# Braille_Cell.net
KiCad netlist of a schematic drawn in EAGLE
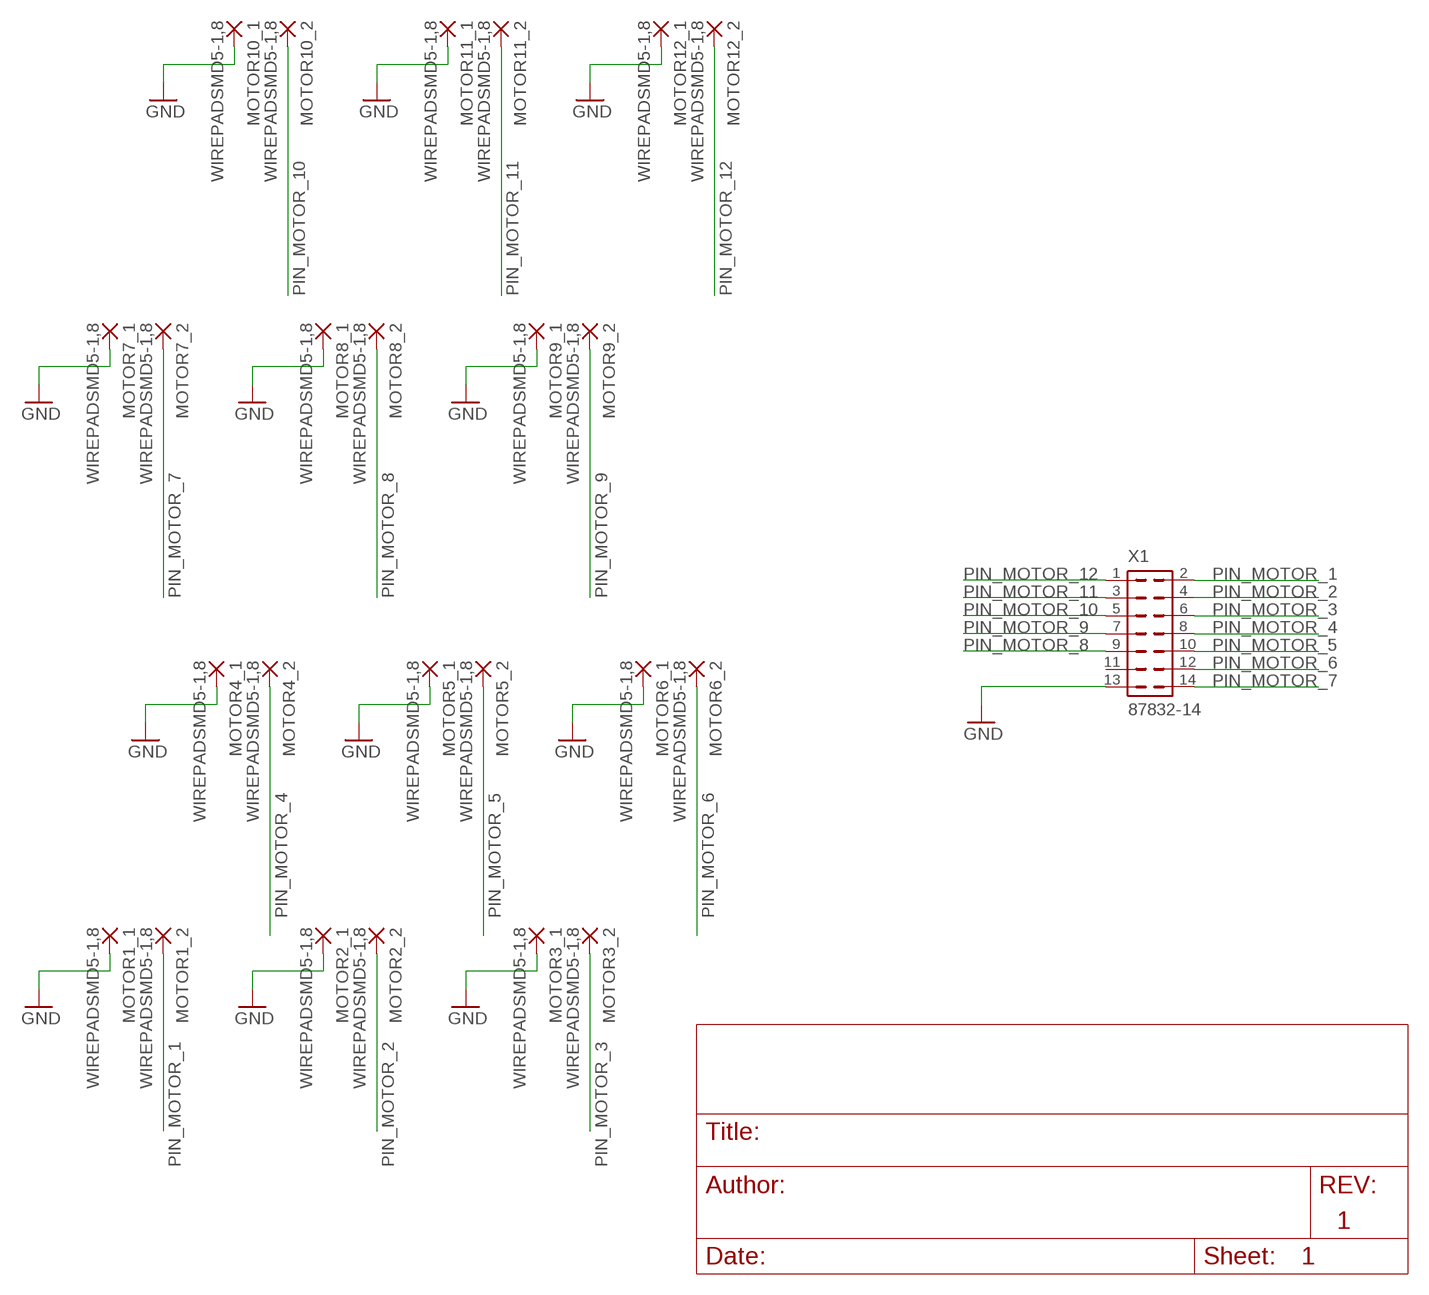
[diagram p0: schematic, sheet 1]

(export (version "E")
  (design (tool "Eeschema 10.0.6"))
  (components
    (comp (ref "MOTOR1_1")
      (value "WIREPADSMD5-1,8")
      (footprint "eagle-import:5-1,8")
      (libsource (lib "eagle-import") (part "WIREPADSMD5-1,8"))
    )
    (comp (ref "MOTOR1_2")
      (value "WIREPADSMD5-1,8")
      (footprint "eagle-import:5-1,8")
      (libsource (lib "eagle-import") (part "WIREPADSMD5-1,8"))
    )
    (comp (ref "MOTOR2_1")
      (value "WIREPADSMD5-1,8")
      (footprint "eagle-import:5-1,8")
      (libsource (lib "eagle-import") (part "WIREPADSMD5-1,8"))
    )
    (comp (ref "MOTOR2_2")
      (value "WIREPADSMD5-1,8")
      (footprint "eagle-import:5-1,8")
      (libsource (lib "eagle-import") (part "WIREPADSMD5-1,8"))
    )
    (comp (ref "MOTOR3_1")
      (value "WIREPADSMD5-1,8")
      (footprint "eagle-import:5-1,8")
      (libsource (lib "eagle-import") (part "WIREPADSMD5-1,8"))
    )
    (comp (ref "MOTOR3_2")
      (value "WIREPADSMD5-1,8")
      (footprint "eagle-import:5-1,8")
      (libsource (lib "eagle-import") (part "WIREPADSMD5-1,8"))
    )
    (comp (ref "MOTOR4_1")
      (value "WIREPADSMD5-1,8")
      (footprint "eagle-import:5-1,8")
      (libsource (lib "eagle-import") (part "WIREPADSMD5-1,8"))
    )
    (comp (ref "MOTOR4_2")
      (value "WIREPADSMD5-1,8")
      (footprint "eagle-import:5-1,8")
      (libsource (lib "eagle-import") (part "WIREPADSMD5-1,8"))
    )
    (comp (ref "MOTOR5_1")
      (value "WIREPADSMD5-1,8")
      (footprint "eagle-import:5-1,8")
      (libsource (lib "eagle-import") (part "WIREPADSMD5-1,8"))
    )
    (comp (ref "MOTOR5_2")
      (value "WIREPADSMD5-1,8")
      (footprint "eagle-import:5-1,8")
      (libsource (lib "eagle-import") (part "WIREPADSMD5-1,8"))
    )
    (comp (ref "MOTOR6_1")
      (value "WIREPADSMD5-1,8")
      (footprint "eagle-import:5-1,8")
      (libsource (lib "eagle-import") (part "WIREPADSMD5-1,8"))
    )
    (comp (ref "MOTOR6_2")
      (value "WIREPADSMD5-1,8")
      (footprint "eagle-import:5-1,8")
      (libsource (lib "eagle-import") (part "WIREPADSMD5-1,8"))
    )
    (comp (ref "MOTOR7_1")
      (value "WIREPADSMD5-1,8")
      (footprint "eagle-import:5-1,8")
      (libsource (lib "eagle-import") (part "WIREPADSMD5-1,8"))
    )
    (comp (ref "MOTOR7_2")
      (value "WIREPADSMD5-1,8")
      (footprint "eagle-import:5-1,8")
      (libsource (lib "eagle-import") (part "WIREPADSMD5-1,8"))
    )
    (comp (ref "MOTOR8_1")
      (value "WIREPADSMD5-1,8")
      (footprint "eagle-import:5-1,8")
      (libsource (lib "eagle-import") (part "WIREPADSMD5-1,8"))
    )
    (comp (ref "MOTOR8_2")
      (value "WIREPADSMD5-1,8")
      (footprint "eagle-import:5-1,8")
      (libsource (lib "eagle-import") (part "WIREPADSMD5-1,8"))
    )
    (comp (ref "MOTOR9_1")
      (value "WIREPADSMD5-1,8")
      (footprint "eagle-import:5-1,8")
      (libsource (lib "eagle-import") (part "WIREPADSMD5-1,8"))
    )
    (comp (ref "MOTOR9_2")
      (value "WIREPADSMD5-1,8")
      (footprint "eagle-import:5-1,8")
      (libsource (lib "eagle-import") (part "WIREPADSMD5-1,8"))
    )
    (comp (ref "MOTOR10_1")
      (value "WIREPADSMD5-1,8")
      (footprint "eagle-import:5-1,8")
      (libsource (lib "eagle-import") (part "WIREPADSMD5-1,8"))
    )
    (comp (ref "MOTOR10_2")
      (value "WIREPADSMD5-1,8")
      (footprint "eagle-import:5-1,8")
      (libsource (lib "eagle-import") (part "WIREPADSMD5-1,8"))
    )
    (comp (ref "MOTOR11_1")
      (value "WIREPADSMD5-1,8")
      (footprint "eagle-import:5-1,8")
      (libsource (lib "eagle-import") (part "WIREPADSMD5-1,8"))
    )
    (comp (ref "MOTOR11_2")
      (value "WIREPADSMD5-1,8")
      (footprint "eagle-import:5-1,8")
      (libsource (lib "eagle-import") (part "WIREPADSMD5-1,8"))
    )
    (comp (ref "MOTOR12_1")
      (value "WIREPADSMD5-1,8")
      (footprint "eagle-import:5-1,8")
      (libsource (lib "eagle-import") (part "WIREPADSMD5-1,8"))
    )
    (comp (ref "MOTOR12_2")
      (value "WIREPADSMD5-1,8")
      (footprint "eagle-import:5-1,8")
      (libsource (lib "eagle-import") (part "WIREPADSMD5-1,8"))
    )
    (comp (ref "X1")
      (value "87832-14")
      (footprint "eagle-import:87832-14")
      (libsource (lib "eagle-import") (part "87832-14"))
    )
  )
  (nets
    (net (code "1") (name "/PIN_MOTOR_1") (class "Default")
      (node (ref "MOTOR1_2") (pin "1") (pinfunction "P_1") (pintype "passive"))
      (node (ref "X1") (pin "2") (pinfunction "2_2") (pintype "passive"))
    )
    (net (code "2") (name "/PIN_MOTOR_2") (class "Default")
      (node (ref "MOTOR2_2") (pin "1") (pinfunction "P_1") (pintype "passive"))
      (node (ref "X1") (pin "4") (pinfunction "4_4") (pintype "passive"))
    )
    (net (code "3") (name "/PIN_MOTOR_3") (class "Default")
      (node (ref "MOTOR3_2") (pin "1") (pinfunction "P_1") (pintype "passive"))
      (node (ref "X1") (pin "6") (pinfunction "6_6") (pintype "passive"))
    )
    (net (code "4") (name "/PIN_MOTOR_4") (class "Default")
      (node (ref "MOTOR4_2") (pin "1") (pinfunction "P_1") (pintype "passive"))
      (node (ref "X1") (pin "8") (pinfunction "8_8") (pintype "passive"))
    )
    (net (code "5") (name "/PIN_MOTOR_5") (class "Default")
      (node (ref "MOTOR5_2") (pin "1") (pinfunction "P_1") (pintype "passive"))
      (node (ref "X1") (pin "10") (pinfunction "10_10") (pintype "passive"))
    )
    (net (code "6") (name "/PIN_MOTOR_6") (class "Default")
      (node (ref "MOTOR6_2") (pin "1") (pinfunction "P_1") (pintype "passive"))
      (node (ref "X1") (pin "12") (pinfunction "12_12") (pintype "passive"))
    )
    (net (code "7") (name "/PIN_MOTOR_7") (class "Default")
      (node (ref "MOTOR7_2") (pin "1") (pinfunction "P_1") (pintype "passive"))
      (node (ref "X1") (pin "14") (pinfunction "14_14") (pintype "passive"))
    )
    (net (code "8") (name "/PIN_MOTOR_8") (class "Default")
      (node (ref "MOTOR8_2") (pin "1") (pinfunction "P_1") (pintype "passive"))
      (node (ref "X1") (pin "9") (pinfunction "9_9") (pintype "passive"))
    )
    (net (code "9") (name "/PIN_MOTOR_9") (class "Default")
      (node (ref "MOTOR9_2") (pin "1") (pinfunction "P_1") (pintype "passive"))
      (node (ref "X1") (pin "7") (pinfunction "7_7") (pintype "passive"))
    )
    (net (code "10") (name "/PIN_MOTOR_10") (class "Default")
      (node (ref "MOTOR10_2") (pin "1") (pinfunction "P_1") (pintype "passive"))
      (node (ref "X1") (pin "5") (pinfunction "5_5") (pintype "passive"))
    )
    (net (code "11") (name "/PIN_MOTOR_11") (class "Default")
      (node (ref "MOTOR11_2") (pin "1") (pinfunction "P_1") (pintype "passive"))
      (node (ref "X1") (pin "3") (pinfunction "3_3") (pintype "passive"))
    )
    (net (code "12") (name "/PIN_MOTOR_12") (class "Default")
      (node (ref "MOTOR12_2") (pin "1") (pinfunction "P_1") (pintype "passive"))
      (node (ref "X1") (pin "1") (pinfunction "1_1") (pintype "passive"))
    )
    (net (code "13") (name "GND") (class "Default")
      (node (ref "MOTOR10_1") (pin "1") (pinfunction "P_1") (pintype "passive"))
      (node (ref "MOTOR11_1") (pin "1") (pinfunction "P_1") (pintype "passive"))
      (node (ref "MOTOR12_1") (pin "1") (pinfunction "P_1") (pintype "passive"))
      (node (ref "MOTOR1_1") (pin "1") (pinfunction "P_1") (pintype "passive"))
      (node (ref "MOTOR2_1") (pin "1") (pinfunction "P_1") (pintype "passive"))
      (node (ref "MOTOR3_1") (pin "1") (pinfunction "P_1") (pintype "passive"))
      (node (ref "MOTOR4_1") (pin "1") (pinfunction "P_1") (pintype "passive"))
      (node (ref "MOTOR5_1") (pin "1") (pinfunction "P_1") (pintype "passive"))
      (node (ref "MOTOR6_1") (pin "1") (pinfunction "P_1") (pintype "passive"))
      (node (ref "MOTOR7_1") (pin "1") (pinfunction "P_1") (pintype "passive"))
      (node (ref "MOTOR8_1") (pin "1") (pinfunction "P_1") (pintype "passive"))
      (node (ref "MOTOR9_1") (pin "1") (pinfunction "P_1") (pintype "passive"))
      (node (ref "X1") (pin "13") (pinfunction "13_13") (pintype "passive"))
    )
    (net (code "14") (name "unconnected-(X1-Pad11)") (class "Default")
      (node (ref "X1") (pin "11") (pinfunction "11_11") (pintype "passive"))
    )
  )
)
